# e3_tp1_ej1.net
KiCad netlist of a schematic drawn in Altium Designer
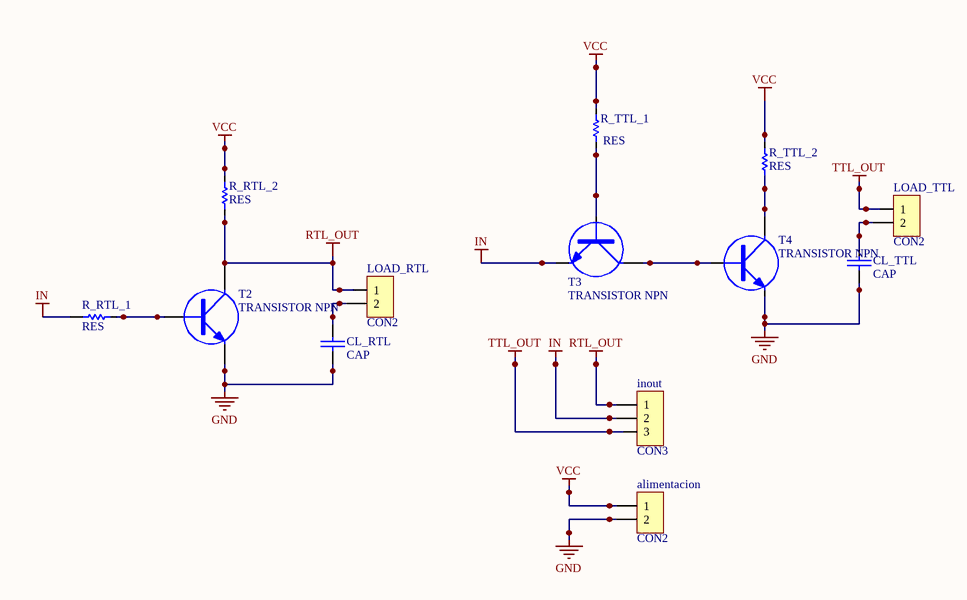
[diagram p0: e3_tp1_ej1.SchDoc]

(export (version "E")
  (design (tool "Eeschema 10.0.6"))
  (components
    (comp (ref "alimentacion") (value "CON2") (footprint "SIP2") (libsource (lib "LIBEBAL") (part "CON2")))
    (comp (ref "CL_RTL") (value "CAP") (footprint "CAP200") (libsource (lib "LIBEBAL") (part "CAP")))
    (comp (ref "CL_TTL") (value "CAP") (footprint "CAP200") (libsource (lib "LIBEBAL") (part "CAP")))
    (comp (ref "inout") (value "CON3") (footprint "SIP3") (libsource (lib "LIBEBAL") (part "CON3")))
    (comp (ref "LOAD_RTL") (value "CON2") (footprint "SIP2") (libsource (lib "LIBEBAL") (part "CON2")))
    (comp (ref "LOAD_TTL") (value "CON2") (footprint "SIP2") (libsource (lib "LIBEBAL") (part "CON2")))
    (comp (ref "R_RTL_1") (value "RES") (footprint "RES300") (libsource (lib "LIBEBAL") (part "RES")))
    (comp (ref "R_RTL_2") (value "RES") (footprint "RES300") (libsource (lib "LIBEBAL") (part "RES")))
    (comp (ref "R_TTL_1") (value "RES") (footprint "RES300") (libsource (lib "LIBEBAL") (part "RES")))
    (comp (ref "R_TTL_2") (value "RES") (footprint "RES300") (libsource (lib "LIBEBAL") (part "RES")))
    (comp (ref "T2")
      (value "TRANSISTOR NPN")
      (footprint "TO92")
      (libsource (lib "LIBEBAL") (part "TRANSISTOR NPN"))
    )
    (comp (ref "T3")
      (value "TRANSISTOR NPN")
      (footprint "TO92")
      (libsource (lib "LIBEBAL") (part "TRANSISTOR NPN"))
    )
    (comp (ref "T4")
      (value "TRANSISTOR NPN")
      (footprint "TO92")
      (libsource (lib "LIBEBAL") (part "TRANSISTOR NPN"))
    )
  )
  (nets
    (net (code "1") (name "GND") (class "Default")
      (node (ref "CL_RTL") (pin "2") (pinfunction "2_2") (pintype "passive"))
      (node (ref "CL_TTL") (pin "2") (pinfunction "2_2") (pintype "passive"))
      (node (ref "T2") (pin "3") (pinfunction "E_3") (pintype "passive"))
      (node (ref "T4") (pin "3") (pinfunction "E_3") (pintype "passive"))
      (node (ref "alimentacion") (pin "2") (pinfunction "2_2") (pintype "passive"))
    )
    (net (code "2") (name "IN") (class "Default")
      (node (ref "R_RTL_1") (pin "1") (pinfunction "1_1") (pintype "passive"))
      (node (ref "T3") (pin "3") (pinfunction "E_3") (pintype "passive"))
      (node (ref "inout") (pin "2") (pinfunction "2_2") (pintype "passive"))
    )
    (net (code "3") (name "Net-(CL_RTL-Pad1)") (class "Default")
      (node (ref "CL_RTL") (pin "1") (pinfunction "1_1") (pintype "passive"))
      (node (ref "LOAD_RTL") (pin "2") (pinfunction "2_2") (pintype "passive"))
    )
    (net (code "4") (name "Net-(CL_TTL-Pad1)") (class "Default")
      (node (ref "CL_TTL") (pin "1") (pinfunction "1_1") (pintype "passive"))
      (node (ref "LOAD_TTL") (pin "2") (pinfunction "2_2") (pintype "passive"))
    )
    (net (code "5") (name "Net-(T2-B)") (class "Default")
      (node (ref "R_RTL_1") (pin "2") (pinfunction "2_2") (pintype "passive"))
      (node (ref "T2") (pin "1") (pinfunction "B_1") (pintype "passive"))
    )
    (net (code "6") (name "Net-(T3-B)") (class "Default")
      (node (ref "R_TTL_1") (pin "1") (pinfunction "1_1") (pintype "passive"))
      (node (ref "T3") (pin "1") (pinfunction "B_1") (pintype "passive"))
    )
    (net (code "7") (name "Net-(T3-C)") (class "Default")
      (node (ref "T3") (pin "2") (pinfunction "C_2") (pintype "passive"))
      (node (ref "T4") (pin "1") (pinfunction "B_1") (pintype "passive"))
    )
    (net (code "8") (name "Net-(T4-C)") (class "Default")
      (node (ref "R_TTL_2") (pin "1") (pinfunction "1_1") (pintype "passive"))
      (node (ref "T4") (pin "2") (pinfunction "C_2") (pintype "passive"))
    )
    (net (code "9") (name "RTL_OUT") (class "Default")
      (node (ref "LOAD_RTL") (pin "1") (pinfunction "1_1") (pintype "passive"))
      (node (ref "R_RTL_2") (pin "1") (pinfunction "1_1") (pintype "passive"))
      (node (ref "T2") (pin "2") (pinfunction "C_2") (pintype "passive"))
      (node (ref "inout") (pin "1") (pinfunction "1_1") (pintype "passive"))
    )
    (net (code "10") (name "TTL_OUT") (class "Default")
      (node (ref "LOAD_TTL") (pin "1") (pinfunction "1_1") (pintype "passive"))
      (node (ref "inout") (pin "3") (pinfunction "3_3") (pintype "passive"))
    )
    (net (code "11") (name "VCC") (class "Default")
      (node (ref "R_RTL_2") (pin "2") (pinfunction "2_2") (pintype "passive"))
      (node (ref "R_TTL_1") (pin "2") (pinfunction "2_2") (pintype "passive"))
      (node (ref "R_TTL_2") (pin "2") (pinfunction "2_2") (pintype "passive"))
      (node (ref "alimentacion") (pin "1") (pinfunction "1_1") (pintype "passive"))
    )
  )
)
